# POWER.net
KiCad netlist of a schematic drawn in Altium Designer
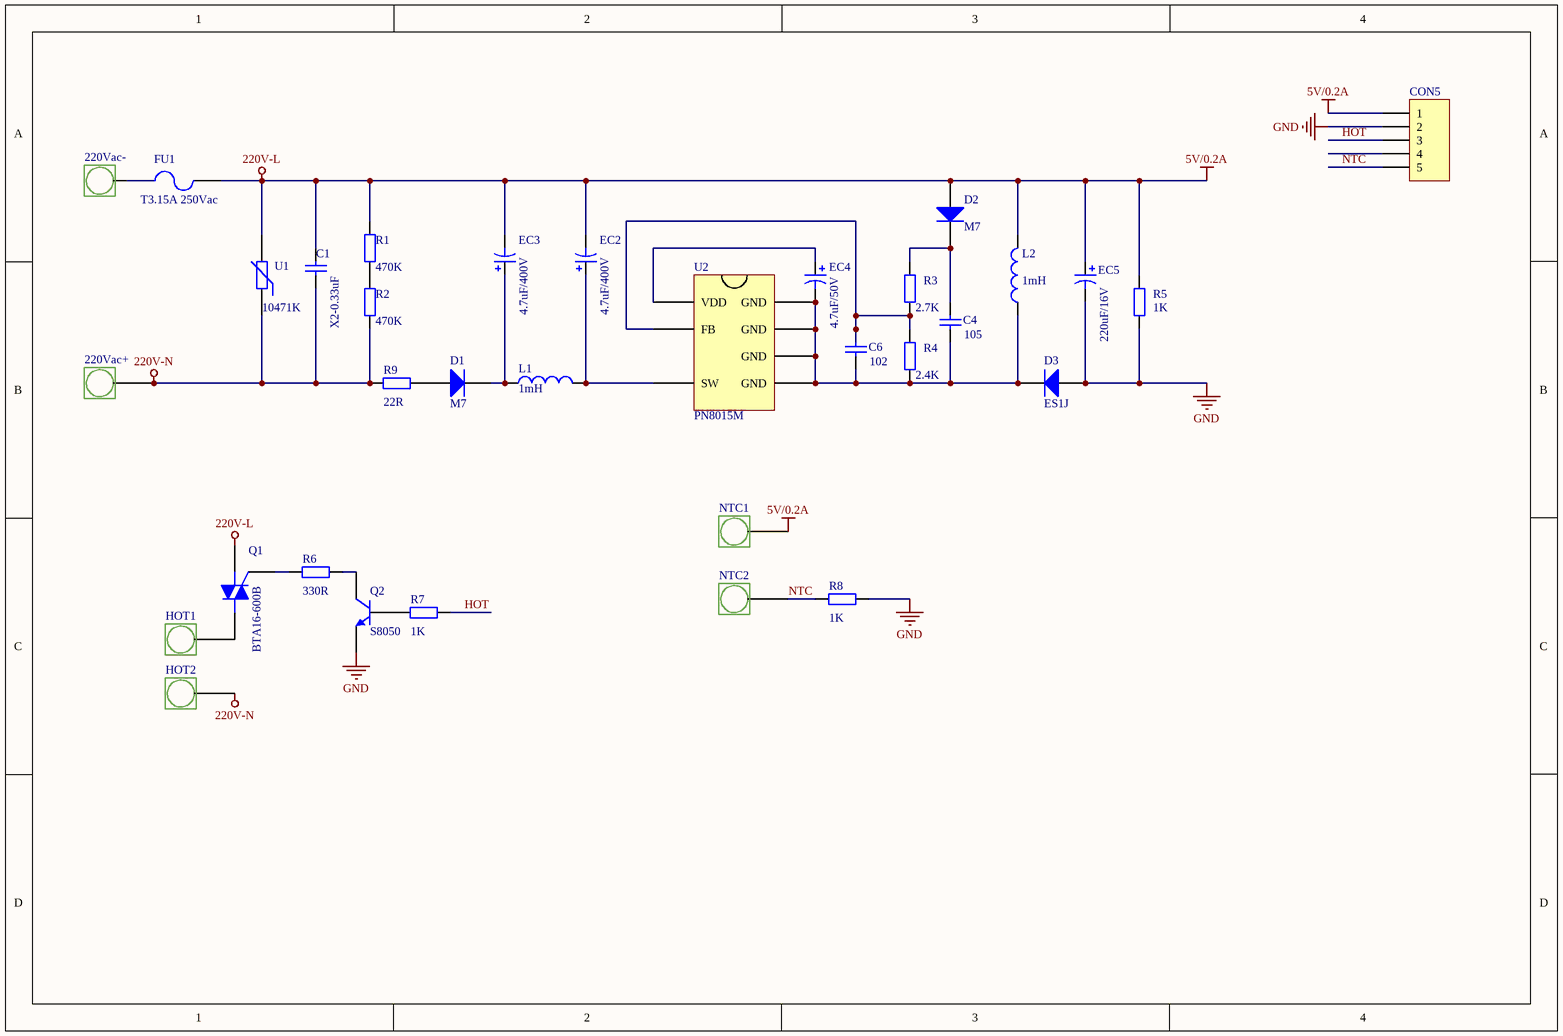
[diagram p0: POWER.SchDoc]

(export (version "E")
  (design (tool "Eeschema 10.0.6"))
  (components
    (comp (ref "220Vac+") (value "焊接点") (footprint "HanJie") (libsource (lib "HT_SHUIHU") (part "PORT")))
    (comp (ref "220Vac-") (value "焊接点") (footprint "HanJie") (libsource (lib "HT_SHUIHU") (part "PORT")))
    (comp (ref "C1")
      (value "X2-0.33uF")
      (footprint "X2-AnGuiDianRong")
      (description "Capacitor")
      (fields (field (name "PUBLISHER") "Altium Limited"))
      (libsource (lib "Miscellaneous Devices") (part "Cap"))
    )
    (comp (ref "C4")
      (value "105")
      (footprint "6-0805_N")
      (description "Capacitor")
      (fields (field (name "Comment") "电容") (field (name "PUBLISHER") "Altium Limited"))
      (libsource (lib "Miscellaneous Devices") (part "Cap"))
    )
    (comp (ref "C6")
      (value "102")
      (footprint "6-0805_N")
      (description "Capacitor")
      (fields (field (name "Comment") "电容") (field (name "PUBLISHER") "Altium Limited"))
      (libsource (lib "Miscellaneous Devices") (part "Cap"))
    )
    (comp (ref "CON5")
      (value "连接器")
      (footprint "HEADER_5")
      (description "Header, 5-Pin")
      (fields (field (name "PUBLISHER") "Altium Limited"))
      (libsource (lib "Miscellaneous Connectors") (part "Header 5"))
    )
    (comp (ref "D1")
      (value "M7")
      (footprint "ErJiGuan-M7")
      (description "1 Amp General Purpose Rectifier")
      (fields (field (name "PUBLISHER") "Altium Limited"))
      (libsource (lib "Miscellaneous Devices") (part "Diode 1N4001"))
    )
    (comp (ref "D2")
      (value "M7")
      (footprint "ErJiGuan-M7")
      (description "1 Amp General Purpose Rectifier")
      (fields (field (name "PUBLISHER") "Altium Limited"))
      (libsource (lib "Miscellaneous Devices") (part "Diode 1N4007"))
    )
    (comp (ref "D3")
      (value "ES1J")
      (footprint "ErJiGuan-M7")
      (description "Default Diode")
      (fields (field (name "PUBLISHER") "Altium Limited"))
      (libsource (lib "Miscellaneous Devices") (part "Diode"))
    )
    (comp (ref "EC2")
      (value "4.7uF/400V")
      (footprint "DianRong-3.5mm")
      (description "Polarized Capacitor (Radial)")
      (fields (field (name "Comment") "电容") (field (name "PUBLISHER") "Altium Limited"))
      (libsource (lib "Miscellaneous Devices") (part "Cap Pol1"))
    )
    (comp (ref "EC3")
      (value "4.7uF/400V")
      (footprint "DianRong-3.5mm")
      (description "Polarized Capacitor (Radial)")
      (fields (field (name "Comment") "电容") (field (name "PUBLISHER") "Altium Limited"))
      (libsource (lib "Miscellaneous Devices") (part "Cap Pol1"))
    )
    (comp (ref "EC4")
      (value "4.7uF/50V")
      (footprint "DianRong-3.3mm")
      (description "Polarized Capacitor (Radial)")
      (fields (field (name "Comment") "电容") (field (name "PUBLISHER") "Altium Limited"))
      (libsource (lib "Miscellaneous Devices") (part "Cap Pol1"))
    )
    (comp (ref "EC5")
      (value "220uF/16V")
      (footprint "DianRong-3.2mm")
      (description "Polarized Capacitor (Radial)")
      (fields (field (name "Comment") "电容") (field (name "PUBLISHER") "Altium Limited"))
      (libsource (lib "Miscellaneous Devices") (part "Cap Pol1"))
    )
    (comp (ref "FU1")
      (value "T3.15A 250Vac")
      (footprint "BaoXianSi")
      (description "Fuse")
      (fields (field (name "PUBLISHER") "Altium Limited"))
      (libsource (lib "Miscellaneous Devices") (part "Fuse 2"))
    )
    (comp (ref "HOT1") (value "焊接点") (footprint "HanJie") (libsource (lib "HT_SHUIHU") (part "PORT")))
    (comp (ref "HOT2") (value "焊接点") (footprint "HanJie") (libsource (lib "HT_SHUIHU") (part "PORT")))
    (comp (ref "L1")
      (value "1mH")
      (footprint "DianGan-12.5mm")
      (description "Inductor")
      (fields (field (name "Comment") "电感") (field (name "PUBLISHER") "Altium Limited"))
      (libsource (lib "Miscellaneous Devices") (part "Inductor"))
    )
    (comp (ref "L2")
      (value "1mH")
      (footprint "DianGan")
      (description "Inductor")
      (fields (field (name "Comment") "电感") (field (name "PUBLISHER") "Altium Limited"))
      (libsource (lib "Miscellaneous Devices") (part "Inductor"))
    )
    (comp (ref "NTC1") (value "焊接点") (footprint "HanJie") (libsource (lib "HT_SHUIHU") (part "PORT")))
    (comp (ref "NTC2") (value "焊接点") (footprint "HanJie") (libsource (lib "HT_SHUIHU") (part "PORT")))
    (comp (ref "Q1")
      (value "BTA16-600B")
      (footprint "BTA16-600B")
      (description "Silicon Bidirectional Triode Thyristor")
      (fields (field (name "PUBLISHER") "Altium Limited"))
      (libsource (lib "Miscellaneous Devices") (part "Triac"))
    )
    (comp (ref "Q2")
      (value "S8050")
      (footprint "SOT-23_L")
      (description "NPN Bipolar Transistor")
      (fields (field (name "PUBLISHER") "Altium Limited"))
      (libsource (lib "Miscellaneous Devices") (part "QNPN"))
    )
    (comp (ref "R1")
      (value "470K")
      (footprint "6-0805_N")
      (description "Resistor")
      (fields (field (name "Comment") "电阻") (field (name "PUBLISHER") "Altium Limited"))
      (libsource (lib "Miscellaneous Devices") (part "Res2"))
    )
    (comp (ref "R2")
      (value "470K")
      (footprint "6-0805_N")
      (description "Resistor")
      (fields (field (name "Comment") "电阻") (field (name "PUBLISHER") "Altium Limited"))
      (libsource (lib "Miscellaneous Devices") (part "Res2"))
    )
    (comp (ref "R3")
      (value "2.7K")
      (footprint "6-0805_N")
      (description "Resistor")
      (fields (field (name "Comment") "电阻") (field (name "PUBLISHER") "Altium Limited"))
      (libsource (lib "Miscellaneous Devices") (part "Res2"))
    )
    (comp (ref "R4")
      (value "2.4K")
      (footprint "6-0805_N")
      (description "Resistor")
      (fields (field (name "Comment") "电阻") (field (name "PUBLISHER") "Altium Limited"))
      (libsource (lib "Miscellaneous Devices") (part "Res2"))
    )
    (comp (ref "R5")
      (value "1K")
      (footprint "6-0805_N")
      (description "Resistor")
      (fields (field (name "Comment") "电阻") (field (name "PUBLISHER") "Altium Limited"))
      (libsource (lib "Miscellaneous Devices") (part "Res2"))
    )
    (comp (ref "R6")
      (value "330R")
      (footprint "6-0805_N")
      (description "Resistor")
      (fields (field (name "Comment") "电阻") (field (name "PUBLISHER") "Altium Limited"))
      (libsource (lib "") (part "Res2_1"))
    )
    (comp (ref "R7")
      (value "1K")
      (footprint "6-0805_N")
      (description "Resistor")
      (fields (field (name "Comment") "电阻") (field (name "PUBLISHER") "Altium Limited"))
      (libsource (lib "") (part "Res2_1"))
    )
    (comp (ref "R8")
      (value "1K")
      (footprint "6-0805_N")
      (description "Resistor")
      (fields (field (name "Comment") "电阻") (field (name "PUBLISHER") "Altium Limited"))
      (libsource (lib "") (part "Res2_1"))
    )
    (comp (ref "R9")
      (value "22R")
      (footprint "DianZhu-20mm")
      (description "Resistor")
      (fields (field (name "Comment") "电阻") (field (name "PUBLISHER") "Altium Limited"))
      (libsource (lib "") (part "Res2_1"))
    )
    (comp (ref "U1")
      (value "10471K")
      (footprint "YaMinDianZhu")
      (description "Varistor (Voltage-Sensitive Resistor)")
      (fields (field (name "PUBLISHER") "Altium Limited"))
      (libsource (lib "Miscellaneous Devices") (part "Res Varistor"))
    )
    (comp (ref "U2")
      (value "PN8015M")
      (footprint "SOP7-PN8015M")
      (libsource (lib "HT_SHUIHU") (part "PN8015"))
    )
  )
  (nets
    (net (code "1") (name "/HOT") (class "Default")
      (node (ref "CON5") (pin "3") (pinfunction "3_3") (pintype "passive"))
      (node (ref "R7") (pin "2") (pinfunction "2_2") (pintype "passive"))
    )
    (net (code "2") (name "/NTC") (class "Default")
      (node (ref "CON5") (pin "5") (pinfunction "5_5") (pintype "passive"))
      (node (ref "NTC2") (pin "1") (pinfunction "P_1") (pintype "passive"))
      (node (ref "R8") (pin "1") (pinfunction "1_1") (pintype "passive"))
    )
    (net (code "3") (name "220V-L") (class "Default")
      (node (ref "C1") (pin "2") (pinfunction "2_2") (pintype "passive"))
      (node (ref "CON5") (pin "1") (pinfunction "1_1") (pintype "passive"))
      (node (ref "D2") (pin "1") (pinfunction "A_1") (pintype "passive"))
      (node (ref "EC2") (pin "2") (pinfunction "2_2") (pintype "passive"))
      (node (ref "EC3") (pin "2") (pinfunction "2_2") (pintype "passive"))
      (node (ref "EC5") (pin "1") (pinfunction "1_1") (pintype "passive"))
      (node (ref "FU1") (pin "2") (pinfunction "2_2") (pintype "passive"))
      (node (ref "L2") (pin "2") (pinfunction "2_2") (pintype "passive"))
      (node (ref "NTC1") (pin "1") (pinfunction "P_1") (pintype "passive"))
      (node (ref "Q1") (pin "1") (pinfunction "M1_1") (pintype "passive"))
      (node (ref "R1") (pin "2") (pinfunction "2_2") (pintype "passive"))
      (node (ref "R5") (pin "2") (pinfunction "2_2") (pintype "passive"))
      (node (ref "U1") (pin "2") (pinfunction "2_2") (pintype "passive"))
    )
    (net (code "4") (name "220V-N") (class "Default")
      (node (ref "220Vac+") (pin "1") (pinfunction "P_1") (pintype "passive"))
      (node (ref "C1") (pin "1") (pinfunction "1_1") (pintype "passive"))
      (node (ref "HOT2") (pin "1") (pinfunction "P_1") (pintype "passive"))
      (node (ref "R2") (pin "1") (pinfunction "1_1") (pintype "passive"))
      (node (ref "R9") (pin "1") (pinfunction "1_1") (pintype "passive"))
      (node (ref "U1") (pin "1") (pinfunction "1_1") (pintype "passive"))
    )
    (net (code "5") (name "GND") (class "Default")
      (node (ref "CON5") (pin "2") (pinfunction "2_2") (pintype "passive"))
      (node (ref "D3") (pin "1") (pinfunction "A_1") (pintype "passive"))
      (node (ref "EC5") (pin "2") (pinfunction "2_2") (pintype "passive"))
      (node (ref "Q2") (pin "2") (pinfunction "E_2") (pintype "passive"))
      (node (ref "R5") (pin "1") (pinfunction "1_1") (pintype "passive"))
      (node (ref "R8") (pin "2") (pinfunction "2_2") (pintype "passive"))
    )
    (net (code "6") (name "Net-(220Vac--P)") (class "Default")
      (node (ref "220Vac-") (pin "1") (pinfunction "P_1") (pintype "passive"))
      (node (ref "FU1") (pin "1") (pinfunction "1_1") (pintype "passive"))
    )
    (net (code "7") (name "Net-(D1-A)") (class "Default")
      (node (ref "D1") (pin "1") (pinfunction "A_1") (pintype "passive"))
      (node (ref "R9") (pin "2") (pinfunction "2_2") (pintype "passive"))
    )
    (net (code "8") (name "Net-(D1-K)") (class "Default")
      (node (ref "D1") (pin "2") (pinfunction "K_2") (pintype "passive"))
      (node (ref "EC3") (pin "1") (pinfunction "1_1") (pintype "passive"))
      (node (ref "L1") (pin "1") (pinfunction "1_1") (pintype "passive"))
    )
    (net (code "9") (name "Net-(D2-K)") (class "Default")
      (node (ref "C4") (pin "2") (pinfunction "2_2") (pintype "passive"))
      (node (ref "D2") (pin "2") (pinfunction "K_2") (pintype "passive"))
      (node (ref "R3") (pin "2") (pinfunction "2_2") (pintype "passive"))
    )
    (net (code "10") (name "Net-(D3-K)") (class "Default")
      (node (ref "C4") (pin "1") (pinfunction "1_1") (pintype "passive"))
      (node (ref "C6") (pin "1") (pinfunction "1_1") (pintype "passive"))
      (node (ref "D3") (pin "2") (pinfunction "K_2") (pintype "passive"))
      (node (ref "EC4") (pin "2") (pinfunction "2_2") (pintype "passive"))
      (node (ref "L2") (pin "1") (pinfunction "1_1") (pintype "passive"))
      (node (ref "R4") (pin "1") (pinfunction "1_1") (pintype "passive"))
      (node (ref "U2") (pin "4") (pinfunction "GND_4") (pintype "passive"))
      (node (ref "U2") (pin "5") (pinfunction "GND_5") (pintype "passive"))
      (node (ref "U2") (pin "6") (pinfunction "GND_6") (pintype "passive"))
      (node (ref "U2") (pin "7") (pinfunction "GND_7") (pintype "passive"))
    )
    (net (code "11") (name "Net-(HOT1-P)") (class "Default")
      (node (ref "HOT1") (pin "1") (pinfunction "P_1") (pintype "passive"))
      (node (ref "Q1") (pin "2") (pinfunction "M2_2") (pintype "passive"))
    )
    (net (code "12") (name "Net-(Q1-G)") (class "Default")
      (node (ref "Q1") (pin "3") (pinfunction "G_3") (pintype "passive"))
      (node (ref "R6") (pin "1") (pinfunction "1_1") (pintype "passive"))
    )
    (net (code "13") (name "Net-(Q2-B)") (class "Default")
      (node (ref "Q2") (pin "1") (pinfunction "B_1") (pintype "passive"))
      (node (ref "R7") (pin "1") (pinfunction "1_1") (pintype "passive"))
    )
    (net (code "14") (name "Net-(Q2-C)") (class "Default")
      (node (ref "Q2") (pin "3") (pinfunction "C_3") (pintype "passive"))
      (node (ref "R6") (pin "2") (pinfunction "2_2") (pintype "passive"))
    )
    (net (code "15") (name "Net-(R1-Pad1)") (class "Default")
      (node (ref "R1") (pin "1") (pinfunction "1_1") (pintype "passive"))
      (node (ref "R2") (pin "2") (pinfunction "2_2") (pintype "passive"))
    )
    (net (code "16") (name "Net-(U2-FB)") (class "Default")
      (node (ref "C6") (pin "2") (pinfunction "2_2") (pintype "passive"))
      (node (ref "R3") (pin "1") (pinfunction "1_1") (pintype "passive"))
      (node (ref "R4") (pin "2") (pinfunction "2_2") (pintype "passive"))
      (node (ref "U2") (pin "2") (pinfunction "FB_2") (pintype "passive"))
    )
    (net (code "17") (name "Net-(U2-SW)") (class "Default")
      (node (ref "EC2") (pin "1") (pinfunction "1_1") (pintype "passive"))
      (node (ref "L1") (pin "2") (pinfunction "2_2") (pintype "passive"))
      (node (ref "U2") (pin "3") (pinfunction "SW_3") (pintype "passive"))
    )
    (net (code "18") (name "Net-(U2-VDD)") (class "Default")
      (node (ref "EC4") (pin "1") (pinfunction "1_1") (pintype "passive"))
      (node (ref "U2") (pin "1") (pinfunction "VDD_1") (pintype "passive"))
    )
    (net (code "19") (name "unconnected-(CON5-Pad4)") (class "Default")
      (node (ref "CON5") (pin "4") (pinfunction "4_4") (pintype "passive"))
    )
  )
)
